# MacroKeypad.net
KiCad netlist of a schematic drawn in EAGLE
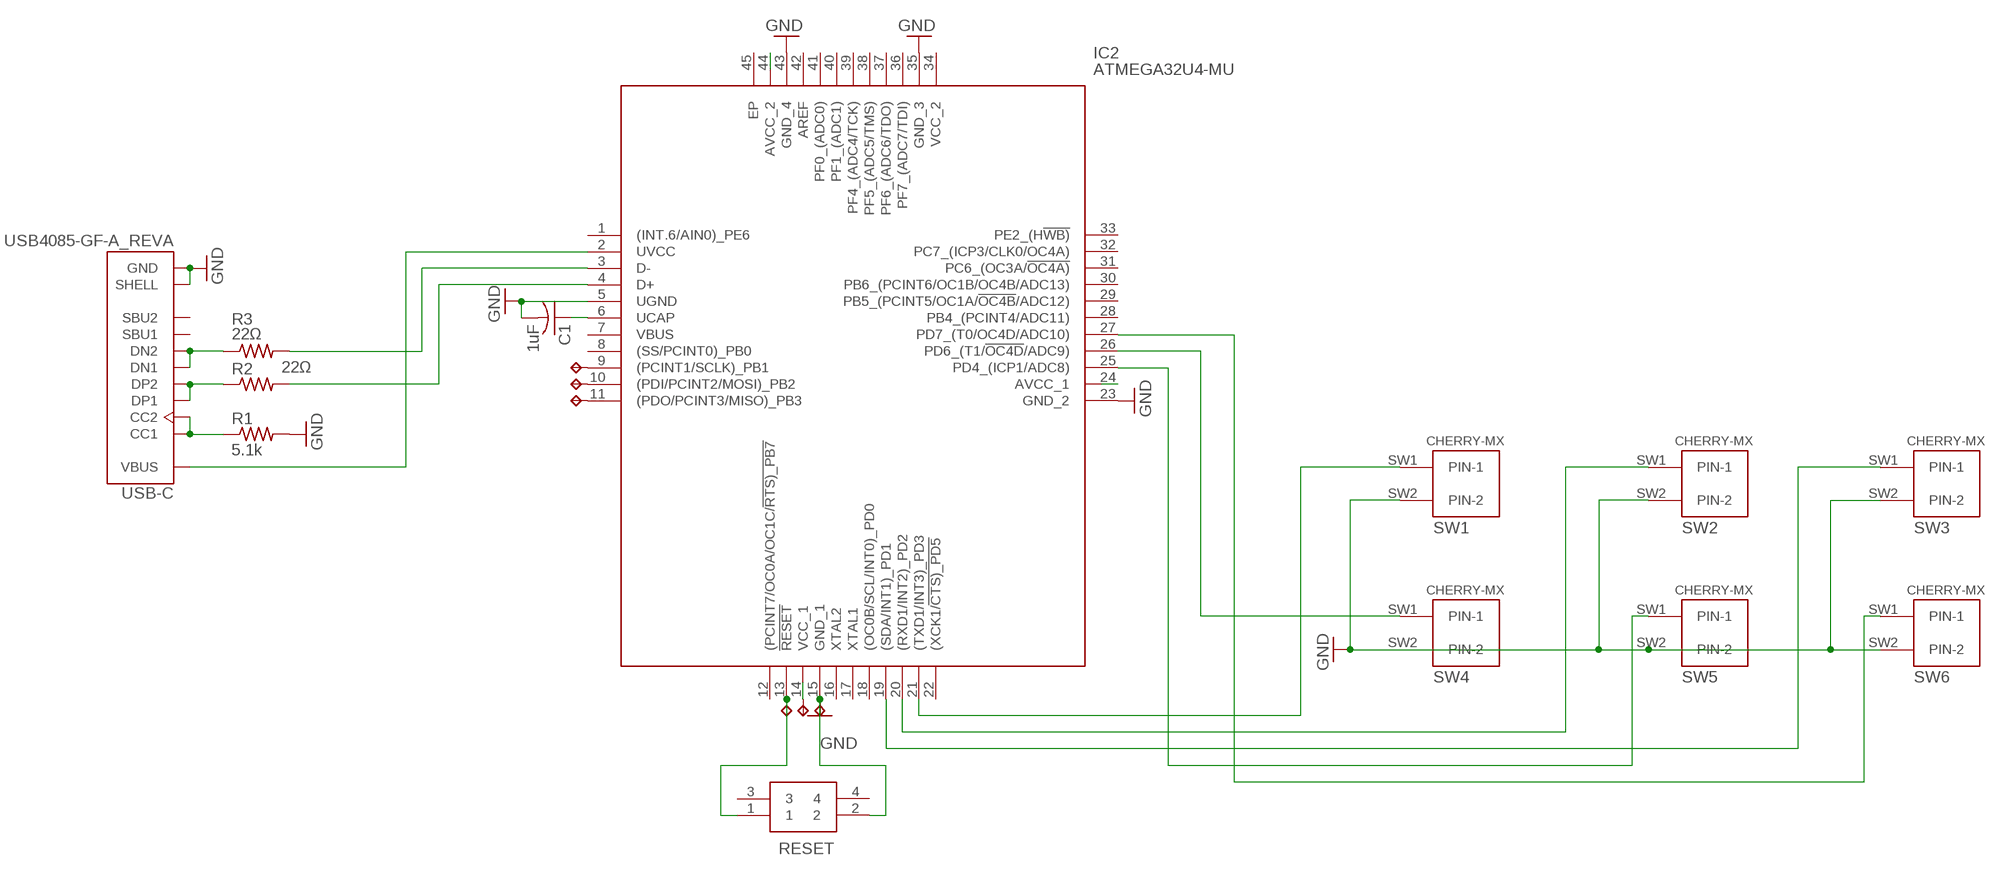
[diagram p0: schematic, sheet 1]

(export (version "E")
  (design (tool "Eeschema 10.0.6"))
  (components
    (comp (ref "5V")
      (value "TPTP17R")
      (footprint "eagle-import:TP17R")
      (libsource (lib "eagle-import") (part "TPTP17R"))
    )
    (comp (ref "C1")
      (value "1uF")
      (footprint "eagle-import:C0805")
      (libsource (lib "eagle-import") (part "C-USC0805"))
    )
    (comp (ref "GND")
      (value "TPTP17R")
      (footprint "eagle-import:TP17R")
      (libsource (lib "eagle-import") (part "TPTP17R"))
    )
    (comp (ref "IC2")
      (value "ATMEGA32U4-MU")
      (footprint "eagle-import:QFN50P700X700X100-45N")
      (fields (field (name "MOUSER_PART_NUMBER") "556-ATMEGA32U4-MU"))
      (libsource (lib "eagle-import") (part "ATMEGA32U4-MU"))
    )
    (comp (ref "MISO")
      (value "TPTP17R")
      (footprint "eagle-import:TP17R")
      (libsource (lib "eagle-import") (part "TPTP17R"))
    )
    (comp (ref "MOSI")
      (value "TPTP17R")
      (footprint "eagle-import:TP17R")
      (libsource (lib "eagle-import") (part "TPTP17R"))
    )
    (comp (ref "R1")
      (value "5.1k")
      (footprint "eagle-import:R0603")
      (libsource (lib "eagle-import") (part "R-US_R0603"))
    )
    (comp (ref "R2")
      (value "22Ω")
      (footprint "eagle-import:R0805")
      (libsource (lib "eagle-import") (part "R-US_R0805"))
    )
    (comp (ref "R3")
      (value "22Ω")
      (footprint "eagle-import:R0805")
      (libsource (lib "eagle-import") (part "R-US_R0805"))
    )
    (comp (ref "RESET")
      (value "LL3303F065QG")
      (footprint "eagle-import:LL3303F065QG")
      (fields (field (name "MOUSER_PART_NUMBER") "612-LL3303F065QG"))
      (libsource (lib "eagle-import") (part "LL3303F065QG"))
    )
    (comp (ref "RST")
      (value "TPTP17R")
      (footprint "eagle-import:TP17R")
      (libsource (lib "eagle-import") (part "TPTP17R"))
    )
    (comp (ref "SCLK")
      (value "TPTP17R")
      (footprint "eagle-import:TP17R")
      (libsource (lib "eagle-import") (part "TPTP17R"))
    )
    (comp (ref "SW1")
      (value "CHERRY-MX")
      (footprint "eagle-import:CHERRY-MX")
      (libsource (lib "eagle-import") (part "CHERRY-MX"))
    )
    (comp (ref "SW2")
      (value "CHERRY-MX")
      (footprint "eagle-import:CHERRY-MX")
      (libsource (lib "eagle-import") (part "CHERRY-MX"))
    )
    (comp (ref "SW3")
      (value "CHERRY-MX")
      (footprint "eagle-import:CHERRY-MX")
      (libsource (lib "eagle-import") (part "CHERRY-MX"))
    )
    (comp (ref "SW4")
      (value "CHERRY-MX")
      (footprint "eagle-import:CHERRY-MX")
      (libsource (lib "eagle-import") (part "CHERRY-MX"))
    )
    (comp (ref "SW5")
      (value "CHERRY-MX")
      (footprint "eagle-import:CHERRY-MX")
      (libsource (lib "eagle-import") (part "CHERRY-MX"))
    )
    (comp (ref "SW6")
      (value "CHERRY-MX")
      (footprint "eagle-import:CHERRY-MX")
      (libsource (lib "eagle-import") (part "CHERRY-MX"))
    )
    (comp (ref "USB-C")
      (value "USB4085-GF-A_REVA")
      (footprint "eagle-import:GCT_USB4085-GF-A_REVA")
      (fields (field (name "MF") "Global Connector Technology") (field (name "MP") "USB4085-GF-A"))
      (libsource (lib "eagle-import") (part "USB4085-GF-A_REVA"))
    )
  )
  (nets
    (net (code "1") (name "/VCC") (class "Default")
      (node (ref "5V") (pin "TP") (pinfunction "TP_TP") (pintype "input"))
      (node (ref "IC2") (pin "14") (pinfunction "VCC_1_14") (pintype "bidirectional"))
      (node (ref "IC2") (pin "24") (pinfunction "AVCC_1_24") (pintype "bidirectional"))
      (node (ref "IC2") (pin "44") (pinfunction "AVCC_2_44") (pintype "bidirectional"))
    )
    (net (code "2") (name "GND") (class "Default")
      (node (ref "C1") (pin "2") (pinfunction "2_2") (pintype "passive"))
      (node (ref "GND") (pin "TP") (pinfunction "TP_TP") (pintype "input"))
      (node (ref "IC2") (pin "15") (pinfunction "GND_1_15") (pintype "bidirectional"))
      (node (ref "IC2") (pin "23") (pinfunction "GND_2_23") (pintype "bidirectional"))
      (node (ref "IC2") (pin "35") (pinfunction "GND_3_35") (pintype "bidirectional"))
      (node (ref "IC2") (pin "43") (pinfunction "GND_4_43") (pintype "bidirectional"))
      (node (ref "IC2") (pin "5") (pinfunction "UGND_5") (pintype "bidirectional"))
      (node (ref "R1") (pin "2") (pinfunction "2_2") (pintype "passive"))
      (node (ref "RESET") (pin "2") (pinfunction "2_2") (pintype "bidirectional"))
      (node (ref "SW1") (pin "SW2") (pinfunction "PIN-2_SW2") (pintype "bidirectional"))
      (node (ref "SW2") (pin "SW2") (pinfunction "PIN-2_SW2") (pintype "bidirectional"))
      (node (ref "SW3") (pin "SW2") (pinfunction "PIN-2_SW2") (pintype "bidirectional"))
      (node (ref "SW4") (pin "SW2") (pinfunction "PIN-2_SW2") (pintype "bidirectional"))
      (node (ref "SW5") (pin "SW2") (pinfunction "PIN-2_SW2") (pintype "bidirectional"))
      (node (ref "SW6") (pin "SW2") (pinfunction "PIN-2_SW2") (pintype "bidirectional"))
      (node (ref "USB-C") (pin "A1") (pinfunction "GND_A1") (pintype "passive"))
      (node (ref "USB-C") (pin "A12") (pinfunction "GND_A12") (pintype "passive"))
      (node (ref "USB-C") (pin "B1") (pinfunction "GND_B1") (pintype "passive"))
      (node (ref "USB-C") (pin "B12") (pinfunction "GND_B12") (pintype "passive"))
      (node (ref "USB-C") (pin "P1") (pinfunction "SHELL_P1") (pintype "passive"))
      (node (ref "USB-C") (pin "P2") (pinfunction "SHELL_P2") (pintype "passive"))
      (node (ref "USB-C") (pin "P3") (pinfunction "SHELL_P3") (pintype "passive"))
      (node (ref "USB-C") (pin "P4") (pinfunction "SHELL_P4") (pintype "passive"))
    )
    (net (code "3") (name "Net-(IC2-(PCINT1{slash}SCLK)_PB1)") (class "Default")
      (node (ref "IC2") (pin "9") (pinfunction "(PCINT1/SCLK)_PB1_9") (pintype "bidirectional"))
      (node (ref "SCLK") (pin "TP") (pinfunction "TP_TP") (pintype "input"))
    )
    (net (code "4") (name "Net-(IC2-(PDI{slash}PCINT2{slash}MOSI)_PB2)") (class "Default")
      (node (ref "IC2") (pin "10") (pinfunction "(PDI/PCINT2/MOSI)_PB2_10") (pintype "bidirectional"))
      (node (ref "MOSI") (pin "TP") (pinfunction "TP_TP") (pintype "input"))
    )
    (net (code "5") (name "Net-(IC2-(PDO{slash}PCINT3{slash}MISO)_PB3)") (class "Default")
      (node (ref "IC2") (pin "11") (pinfunction "(PDO/PCINT3/MISO)_PB3_11") (pintype "bidirectional"))
      (node (ref "MISO") (pin "TP") (pinfunction "TP_TP") (pintype "input"))
    )
    (net (code "6") (name "Net-(IC2-(RXD1{slash}INT2)_PD2)") (class "Default")
      (node (ref "IC2") (pin "20") (pinfunction "(RXD1/INT2)_PD2_20") (pintype "bidirectional"))
      (node (ref "SW2") (pin "SW1") (pinfunction "PIN-1_SW1") (pintype "bidirectional"))
    )
    (net (code "7") (name "Net-(IC2-(SDA{slash}INT1)_PD1)") (class "Default")
      (node (ref "IC2") (pin "19") (pinfunction "(SDA/INT1)_PD1_19") (pintype "bidirectional"))
      (node (ref "SW3") (pin "SW1") (pinfunction "PIN-1_SW1") (pintype "bidirectional"))
    )
    (net (code "8") (name "Net-(IC2-(TXD1{slash}INT3)_PD3)") (class "Default")
      (node (ref "IC2") (pin "21") (pinfunction "(TXD1/INT3)_PD3_21") (pintype "bidirectional"))
      (node (ref "SW1") (pin "SW1") (pinfunction "PIN-1_SW1") (pintype "bidirectional"))
    )
    (net (code "9") (name "Net-(IC2-D+)") (class "Default")
      (node (ref "IC2") (pin "4") (pinfunction "D+_4") (pintype "bidirectional"))
      (node (ref "R2") (pin "2") (pinfunction "2_2") (pintype "passive"))
    )
    (net (code "10") (name "Net-(IC2-D-)") (class "Default")
      (node (ref "IC2") (pin "3") (pinfunction "D-_3") (pintype "bidirectional"))
      (node (ref "R3") (pin "2") (pinfunction "2_2") (pintype "passive"))
    )
    (net (code "11") (name "Net-(IC2-PD4_(ICP1{slash}ADC8))") (class "Default")
      (node (ref "IC2") (pin "25") (pinfunction "PD4_(ICP1/ADC8)_25") (pintype "bidirectional"))
      (node (ref "SW5") (pin "SW1") (pinfunction "PIN-1_SW1") (pintype "bidirectional"))
    )
    (net (code "12") (name "Net-(IC2-PD6_(T1{slash}~{OC4D}{slash}ADC9))") (class "Default")
      (node (ref "IC2") (pin "26") (pinfunction "PD6_(T1/~{OC4D}/ADC9)_26") (pintype "bidirectional"))
      (node (ref "SW4") (pin "SW1") (pinfunction "PIN-1_SW1") (pintype "bidirectional"))
    )
    (net (code "13") (name "Net-(IC2-PD7_(T0{slash}OC4D{slash}ADC10))") (class "Default")
      (node (ref "IC2") (pin "27") (pinfunction "PD7_(T0/OC4D/ADC10)_27") (pintype "bidirectional"))
      (node (ref "SW6") (pin "SW1") (pinfunction "PIN-1_SW1") (pintype "bidirectional"))
    )
    (net (code "14") (name "Net-(IC2-UCAP)") (class "Default")
      (node (ref "C1") (pin "1") (pinfunction "1_1") (pintype "passive"))
      (node (ref "IC2") (pin "6") (pinfunction "UCAP_6") (pintype "bidirectional"))
    )
    (net (code "15") (name "Net-(IC2-UVCC)") (class "Default")
      (node (ref "IC2") (pin "2") (pinfunction "UVCC_2") (pintype "bidirectional"))
      (node (ref "USB-C") (pin "A4") (pinfunction "VBUS_A4") (pintype "power_in"))
      (node (ref "USB-C") (pin "A9") (pinfunction "VBUS_A9") (pintype "power_in"))
      (node (ref "USB-C") (pin "B4") (pinfunction "VBUS_B4") (pintype "power_in"))
      (node (ref "USB-C") (pin "B9") (pinfunction "VBUS_B9") (pintype "power_in"))
    )
    (net (code "16") (name "Net-(IC2-~{RESET})") (class "Default")
      (node (ref "IC2") (pin "13") (pinfunction "~{RESET}_13") (pintype "bidirectional"))
      (node (ref "RESET") (pin "1") (pinfunction "1_1") (pintype "bidirectional"))
      (node (ref "RST") (pin "TP") (pinfunction "TP_TP") (pintype "input"))
    )
    (net (code "17") (name "Net-(USB-C-CC1)") (class "Default")
      (node (ref "R1") (pin "1") (pinfunction "1_1") (pintype "passive"))
      (node (ref "USB-C") (pin "A5") (pinfunction "CC1_A5") (pintype "bidirectional"))
      (node (ref "USB-C") (pin "B5") (pinfunction "CC2_B5") (pintype "bidirectional"))
    )
    (net (code "18") (name "Net-(USB-C-DN1)") (class "Default")
      (node (ref "R3") (pin "1") (pinfunction "1_1") (pintype "passive"))
      (node (ref "USB-C") (pin "A7") (pinfunction "DN1_A7") (pintype "bidirectional"))
      (node (ref "USB-C") (pin "B7") (pinfunction "DN2_B7") (pintype "bidirectional"))
    )
    (net (code "19") (name "Net-(USB-C-DP1)") (class "Default")
      (node (ref "R2") (pin "1") (pinfunction "1_1") (pintype "passive"))
      (node (ref "USB-C") (pin "A6") (pinfunction "DP1_A6") (pintype "bidirectional"))
      (node (ref "USB-C") (pin "B6") (pinfunction "DP2_B6") (pintype "bidirectional"))
    )
    (net (code "20") (name "unconnected-(IC2-(INT.6{slash}AIN0)_PE6-Pad1)") (class "Default")
      (node (ref "IC2") (pin "1") (pinfunction "(INT.6/AIN0)_PE6_1") (pintype "bidirectional"))
    )
    (net (code "21") (name "unconnected-(IC2-(OC0B{slash}SCL{slash}INT0)_PD0-Pad18)") (class "Default")
      (node (ref "IC2") (pin "18") (pinfunction "(OC0B/SCL/INT0)_PD0_18") (pintype "bidirectional"))
    )
    (net (code "22") (name "unconnected-(IC2-(PCINT7{slash}OC0A{slash}OC1C{slash}~{RTS})_PB7-Pad12)") (class "Default")
      (node (ref "IC2") (pin "12") (pinfunction "(PCINT7/OC0A/OC1C/~{RTS})_PB7_12") (pintype "bidirectional"))
    )
    (net (code "23") (name "unconnected-(IC2-(SS{slash}PCINT0)_PB0-Pad8)") (class "Default")
      (node (ref "IC2") (pin "8") (pinfunction "(SS/PCINT0)_PB0_8") (pintype "bidirectional"))
    )
    (net (code "24") (name "unconnected-(IC2-(XCK1{slash}~{CTS})_PD5-Pad22)") (class "Default")
      (node (ref "IC2") (pin "22") (pinfunction "(XCK1/~{CTS})_PD5_22") (pintype "bidirectional"))
    )
    (net (code "25") (name "unconnected-(IC2-AREF-Pad42)") (class "Default")
      (node (ref "IC2") (pin "42") (pinfunction "AREF_42") (pintype "bidirectional"))
    )
    (net (code "26") (name "unconnected-(IC2-EP-Pad45)") (class "Default")
      (node (ref "IC2") (pin "45") (pinfunction "EP_45") (pintype "bidirectional"))
    )
    (net (code "27") (name "unconnected-(IC2-PB4_(PCINT4{slash}ADC11)-Pad28)") (class "Default")
      (node (ref "IC2") (pin "28") (pinfunction "PB4_(PCINT4/ADC11)_28") (pintype "bidirectional"))
    )
    (net (code "28") (name "unconnected-(IC2-PB5_(PCINT5{slash}OC1A{slash}~{OC4B}{slash}ADC12)-Pad29)") (class "Default")
      (node (ref "IC2") (pin "29") (pinfunction "PB5_(PCINT5/OC1A/~{OC4B}/ADC12)_29") (pintype "bidirectional"))
    )
    (net (code "29") (name "unconnected-(IC2-PB6_(PCINT6{slash}OC1B{slash}OC4B{slash}ADC13)-Pad30)") (class "Default")
      (node (ref "IC2") (pin "30") (pinfunction "PB6_(PCINT6/OC1B/OC4B/ADC13)_30") (pintype "bidirectional"))
    )
    (net (code "30") (name "unconnected-(IC2-PC6_(OC3A{slash}~{OC4A})-Pad31)") (class "Default")
      (node (ref "IC2") (pin "31") (pinfunction "PC6_(OC3A/~{OC4A})_31") (pintype "bidirectional"))
    )
    (net (code "31") (name "unconnected-(IC2-PC7_(ICP3{slash}CLK0{slash}OC4A)-Pad32)") (class "Default")
      (node (ref "IC2") (pin "32") (pinfunction "PC7_(ICP3/CLK0/OC4A)_32") (pintype "bidirectional"))
    )
    (net (code "32") (name "unconnected-(IC2-PE2_(H~{WB})-Pad33)") (class "Default")
      (node (ref "IC2") (pin "33") (pinfunction "PE2_(H~{WB})_33") (pintype "bidirectional"))
    )
    (net (code "33") (name "unconnected-(IC2-PF0_(ADC0)-Pad41)") (class "Default")
      (node (ref "IC2") (pin "41") (pinfunction "PF0_(ADC0)_41") (pintype "bidirectional"))
    )
    (net (code "34") (name "unconnected-(IC2-PF1_(ADC1)-Pad40)") (class "Default")
      (node (ref "IC2") (pin "40") (pinfunction "PF1_(ADC1)_40") (pintype "bidirectional"))
    )
    (net (code "35") (name "unconnected-(IC2-PF4_(ADC4{slash}TCK)-Pad39)") (class "Default")
      (node (ref "IC2") (pin "39") (pinfunction "PF4_(ADC4/TCK)_39") (pintype "bidirectional"))
    )
    (net (code "36") (name "unconnected-(IC2-PF5_(ADC5{slash}TMS)-Pad38)") (class "Default")
      (node (ref "IC2") (pin "38") (pinfunction "PF5_(ADC5/TMS)_38") (pintype "bidirectional"))
    )
    (net (code "37") (name "unconnected-(IC2-PF6_(ADC6{slash}TDO)-Pad37)") (class "Default")
      (node (ref "IC2") (pin "37") (pinfunction "PF6_(ADC6/TDO)_37") (pintype "bidirectional"))
    )
    (net (code "38") (name "unconnected-(IC2-PF7_(ADC7{slash}TDI)-Pad36)") (class "Default")
      (node (ref "IC2") (pin "36") (pinfunction "PF7_(ADC7/TDI)_36") (pintype "bidirectional"))
    )
    (net (code "39") (name "unconnected-(IC2-VBUS-Pad7)") (class "Default")
      (node (ref "IC2") (pin "7") (pinfunction "VBUS_7") (pintype "bidirectional"))
    )
    (net (code "40") (name "unconnected-(IC2-VCC_2-Pad34)") (class "Default")
      (node (ref "IC2") (pin "34") (pinfunction "VCC_2_34") (pintype "bidirectional"))
    )
    (net (code "41") (name "unconnected-(IC2-XTAL1-Pad17)") (class "Default")
      (node (ref "IC2") (pin "17") (pinfunction "XTAL1_17") (pintype "bidirectional"))
    )
    (net (code "42") (name "unconnected-(IC2-XTAL2-Pad16)") (class "Default")
      (node (ref "IC2") (pin "16") (pinfunction "XTAL2_16") (pintype "bidirectional"))
    )
    (net (code "43") (name "unconnected-(RESET-Pad3)") (class "Default")
      (node (ref "RESET") (pin "3") (pinfunction "3_3") (pintype "bidirectional"))
    )
    (net (code "44") (name "unconnected-(RESET-Pad4)") (class "Default")
      (node (ref "RESET") (pin "4") (pinfunction "4_4") (pintype "bidirectional"))
    )
    (net (code "45") (name "unconnected-(USB-C-SBU1-PadA8)") (class "Default")
      (node (ref "USB-C") (pin "A8") (pinfunction "SBU1_A8") (pintype "bidirectional"))
    )
    (net (code "46") (name "unconnected-(USB-C-SBU2-PadB8)") (class "Default")
      (node (ref "USB-C") (pin "B8") (pinfunction "SBU2_B8") (pintype "bidirectional"))
    )
  )
)
